# EIGHT_29.net
KiCad netlist of a schematic drawn in Altium Designer
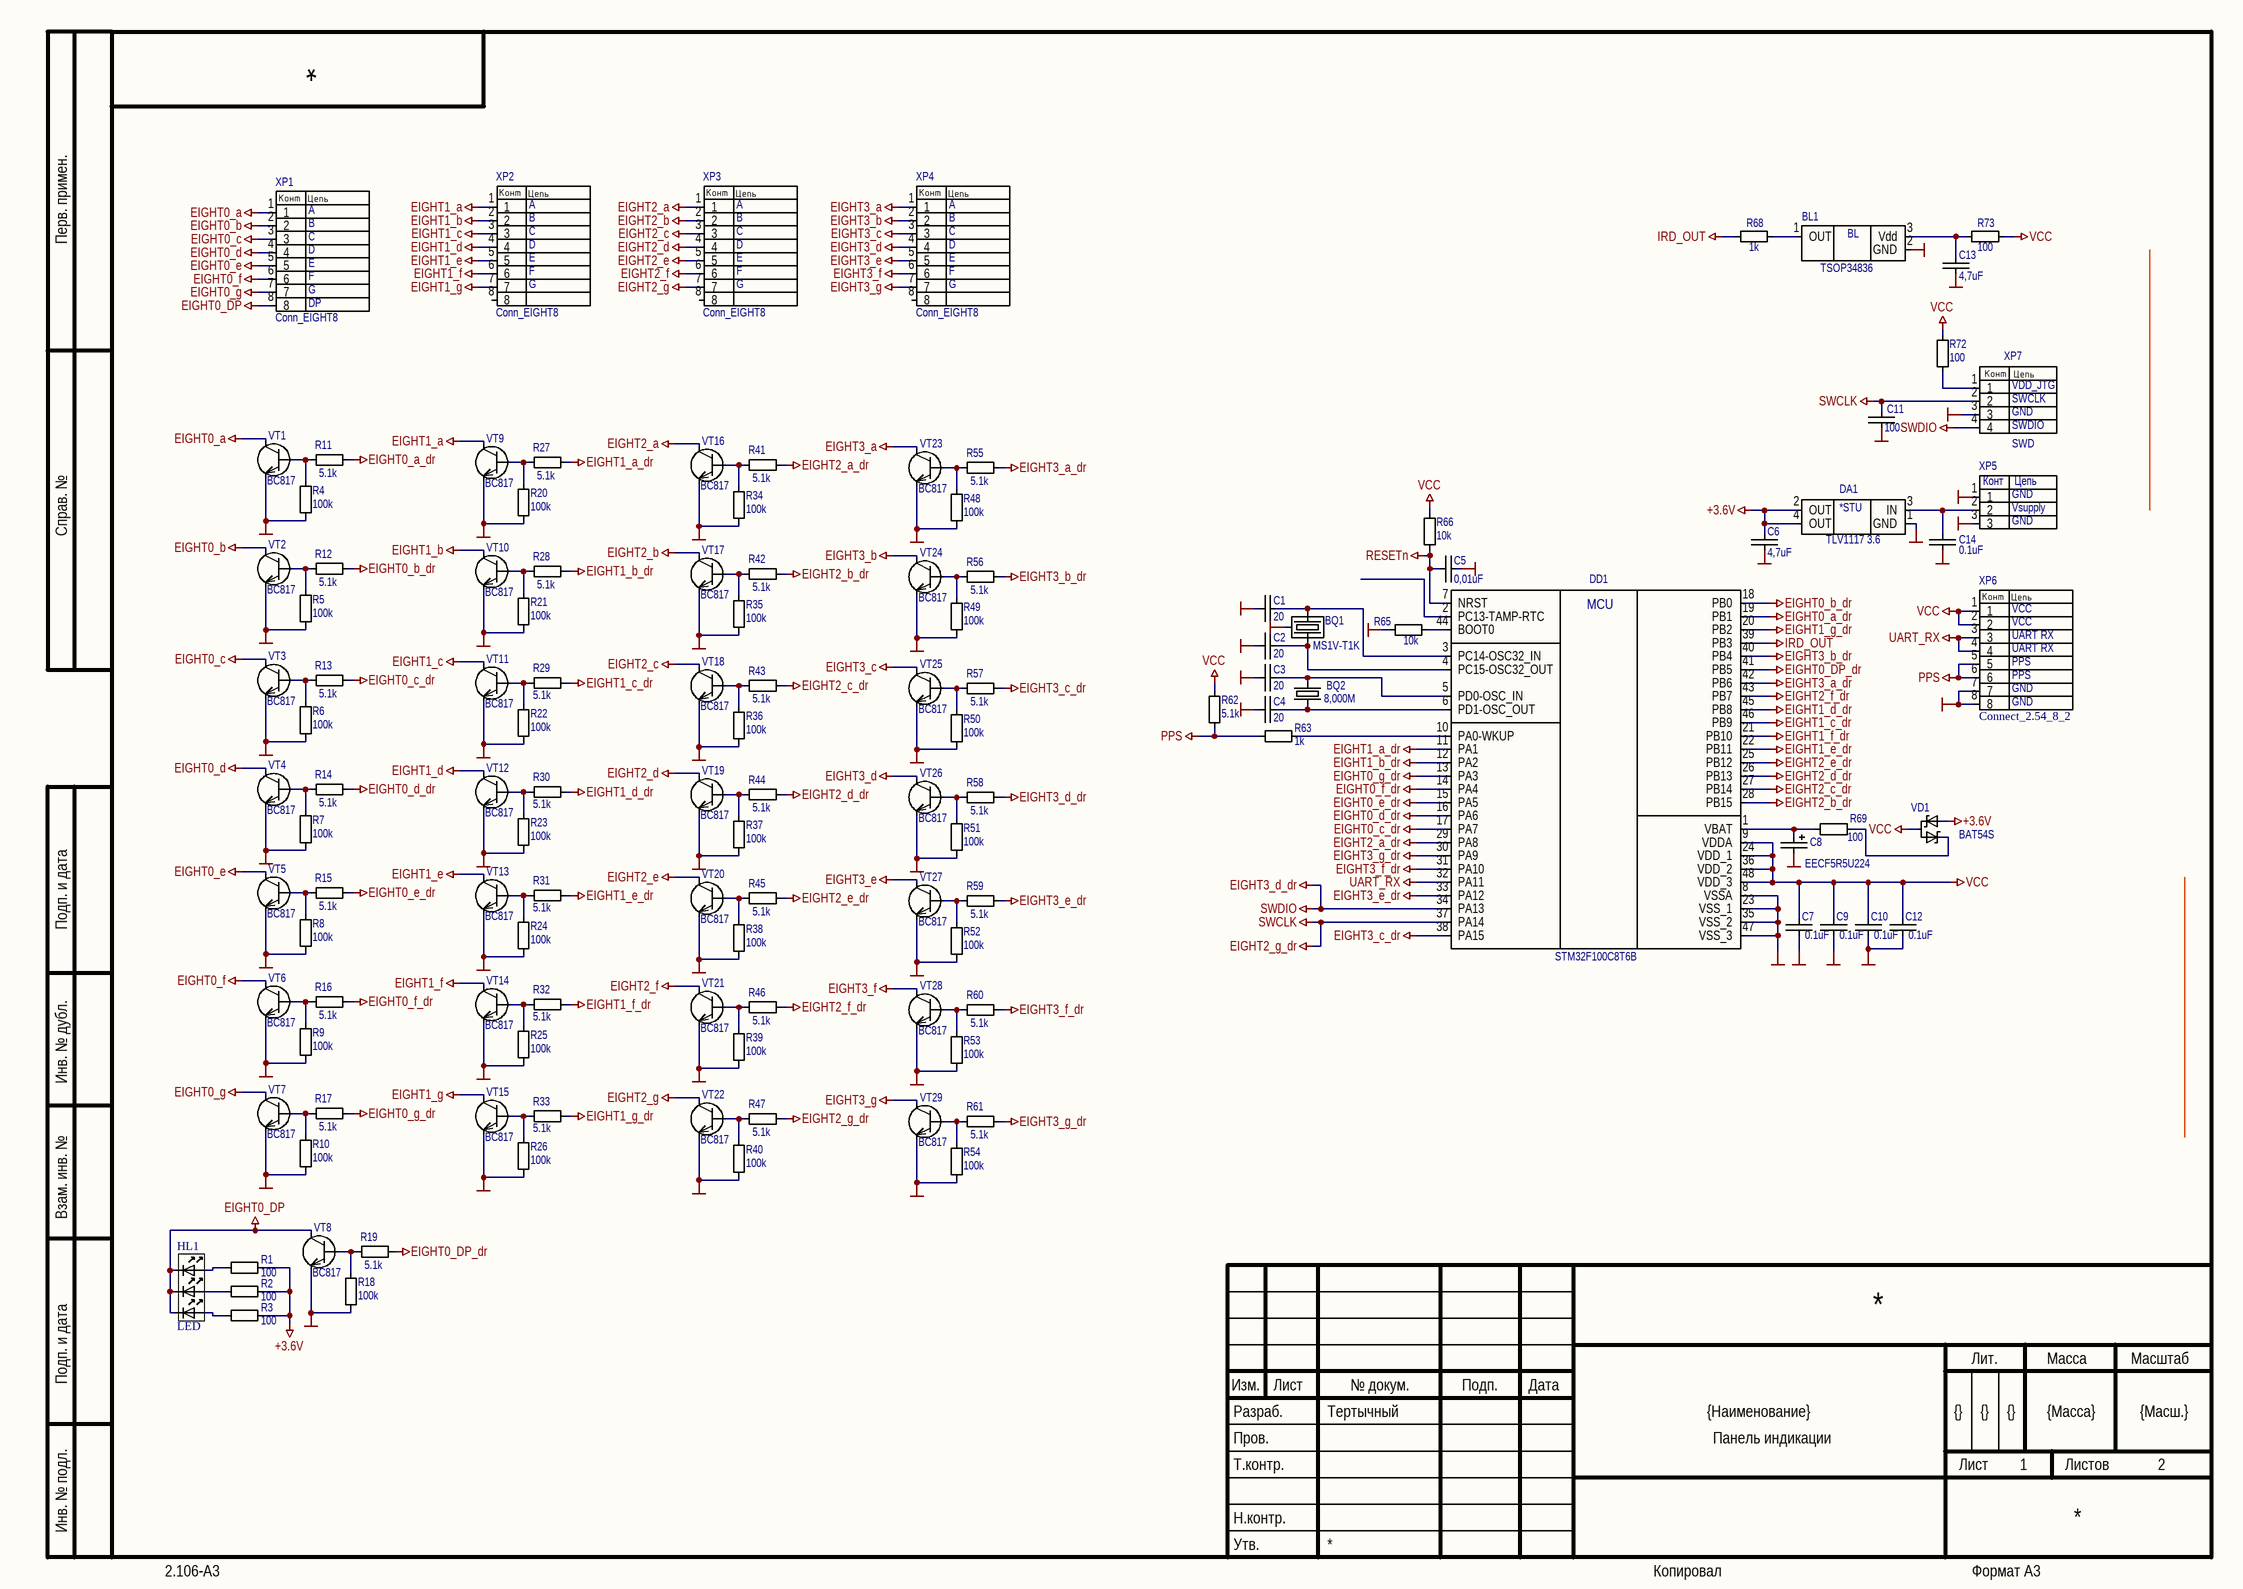
[diagram p0: EIGHT_29.SchDoc]

(export (version "E")
  (design (tool "Eeschema 10.0.6"))
  (components
    (comp (ref "BL1")
      (value "TSOP34836")
      (footprint "TSOP348xx -landed")
      (description "IR Receiver module")
      (fields (field (name "MANUFACTURER") "Vishay"))
      (libsource (lib "PANEL") (part "TSOP348xx_landed"))
    )
    (comp (ref "BQ1")
      (value "MS1V-T1K")
      (footprint "Quartz32k")
      (description "MS1V-T1K Quartz 32kHz 6pF")
      (fields (field (name "PART NUMBER") "MS1V-T1K 32.768kHZ 7pF"))
      (libsource (lib "PANEL") (part "MS1V-T1K"))
    )
    (comp (ref "BQ2")
      (value "8,000M")
      (footprint "HC 49SM")
      (description "Crystal oscillator")
      (fields (field (name "MANUFACTURER") "STRONG") (field (name "PART NUMBER") "HC49SM-8.000MHZ-20PF"))
      (libsource (lib "PANEL") (part "BQ_HC 49SM"))
    )
    (comp (ref "C1")
      (value "20")
      (footprint "Cap_0805")
      (description "20pF 100V 5% NPO")
      (fields (field (name "MANUFACTURER") "AVX") (field (name "PART NUMBER") "GRM2165C1H200J"))
      (libsource (lib "PANEL") (part "Cap_0805"))
    )
    (comp (ref "C2")
      (value "20")
      (footprint "Cap_0805")
      (description "20pF 100V 5% NPO")
      (fields (field (name "MANUFACTURER") "AVX") (field (name "PART NUMBER") "GRM2165C1H200J"))
      (libsource (lib "PANEL") (part "Cap_0805"))
    )
    (comp (ref "C3")
      (value "20")
      (footprint "Cap_0805")
      (description "20pF 100V 5% NPO")
      (fields (field (name "MANUFACTURER") "AVX") (field (name "PART NUMBER") "GRM2165C1H200J"))
      (libsource (lib "PANEL") (part "Cap_0805"))
    )
    (comp (ref "C4")
      (value "20")
      (footprint "Cap_0805")
      (description "20pF 100V 5% NPO")
      (fields (field (name "MANUFACTURER") "AVX") (field (name "PART NUMBER") "GRM2165C1H200J"))
      (libsource (lib "PANEL") (part "Cap_0805"))
    )
    (comp (ref "C5")
      (value "0,01uF")
      (footprint "Cap_0805")
      (description "0805 0.01uF 10V X7R 10%")
      (fields (field (name "MANUFACTURER") "AVX") (field (name "PART NUMBER") "08051C103KAT2A"))
      (libsource (lib "PANEL") (part "Cap_0805"))
    )
    (comp (ref "C6")
      (value "4,7uF")
      (footprint "Cap_0805")
      (description "4.7uF 16V X7R 10%")
      (fields (field (name "MANUFACTURER") "AVX") (field (name "PART NUMBER") "0805YC475KAT2A"))
      (libsource (lib "PANEL") (part "Cap_0805"))
    )
    (comp (ref "C7") (value "0.1uF") (footprint "CAP_0805") (libsource (lib "EIGHT_29") (part "Cap_0805")))
    (comp (ref "C8")
      (value "EECF5R5U224")
      (footprint "EECF5R5U224")
      (fields (field (name "MANUFACTURER") "PANASONIC"))
      (libsource (lib "EIGHT_29") (part "EECF5R5U224"))
    )
    (comp (ref "C9") (value "0.1uF") (footprint "CAP_0805") (libsource (lib "EIGHT_29") (part "Cap_0805")))
    (comp (ref "C10") (value "0.1uF") (footprint "CAP_0805") (libsource (lib "EIGHT_29") (part "Cap_0805")))
    (comp (ref "C11")
      (value "100")
      (footprint "Cap_0805")
      (description "0805 100pF 50V X7R 10%")
      (fields (field (name "MANUFACTURER") "AVX") (field (name "PART NUMBER") "08055C101KAT2A"))
      (libsource (lib "PANEL") (part "Cap_0805"))
    )
    (comp (ref "C12") (value "0.1uF") (footprint "CAP_0805") (libsource (lib "EIGHT_29") (part "Cap_0805")))
    (comp (ref "C13")
      (value "4,7uF")
      (footprint "Cap_0805")
      (description "4.7uF 16V X7R 10%")
      (fields (field (name "MANUFACTURER") "AVX") (field (name "PART NUMBER") "0805YC475KAT2A"))
      (libsource (lib "PANEL") (part "Cap_0805"))
    )
    (comp (ref "C14") (value "0.1uF") (footprint "CAP_0805") (libsource (lib "EIGHT_29") (part "Cap_0805")))
    (comp (ref "DA1")
      (value "TLV1117 3.6")
      (footprint "SOT223")
      (description "TLV1117-sot223")
      (fields (field (name "MANUFACTURER") "Microchip") (field (name "PART NUMBER") "TLV1117"))
      (libsource (lib "EIGHT_29") (part "TLV1117"))
    )
    (comp (ref "DD1")
      (value "STM32F100C8T6B")
      (footprint "LQFP48")
      (description "ARM Cortex-M3 MCU")
      (fields (field (name "MANUFACTURER") "ST"))
      (libsource (lib "PANEL") (part "STM32F100C8T6B"))
    )
    (comp (ref "HL1")
      (value "LED")
      (footprint "LED5050")
      (description "SMD5050")
      (fields (field (name "MANUFACTURER") "DIODES"))
      (libsource (lib "EIGHT_29") (part "LED SMD5050"))
    )
    (comp (ref "R1")
      (value "100")
      (footprint "Res_0603")
      (description "0805 0.125W 100 Ohms 5%")
      (fields (field (name "MANUFACTURER") "Vishay") (field (name "PART NUMBER") "CRCW0805100RJNEA"))
      (libsource (lib "PANEL") (part "Res_0805"))
    )
    (comp (ref "R2")
      (value "100")
      (footprint "Res_0603")
      (description "0805 0.125W 100 Ohms 5%")
      (fields (field (name "MANUFACTURER") "Vishay") (field (name "PART NUMBER") "CRCW0805100RJNEA"))
      (libsource (lib "PANEL") (part "Res_0805"))
    )
    (comp (ref "R3")
      (value "100")
      (footprint "Res_0603")
      (description "0805 0.125W 100 Ohms 5%")
      (fields (field (name "MANUFACTURER") "Vishay") (field (name "PART NUMBER") "CRCW0805100RJNEA"))
      (libsource (lib "PANEL") (part "Res_0805"))
    )
    (comp (ref "R4")
      (value "100k")
      (footprint "Res_0603")
      (description "0805, 0.125W, 100 kOhm, 5 %")
      (fields (field (name "MANUFACTURER") "Bourns") (field (name "PART NUMBER") "CR0805-JW-104ELF"))
      (libsource (lib "PANEL") (part "Res_0805"))
    )
    (comp (ref "R5")
      (value "100k")
      (footprint "Res_0603")
      (description "0805, 0.125W, 100 kOhm, 5 %")
      (fields (field (name "MANUFACTURER") "Bourns") (field (name "PART NUMBER") "CR0805-JW-104ELF"))
      (libsource (lib "PANEL") (part "Res_0805"))
    )
    (comp (ref "R6")
      (value "100k")
      (footprint "Res_0603")
      (description "0805, 0.125W, 100 kOhm, 5 %")
      (fields (field (name "MANUFACTURER") "Bourns") (field (name "PART NUMBER") "CR0805-JW-104ELF"))
      (libsource (lib "PANEL") (part "Res_0805"))
    )
    (comp (ref "R7")
      (value "100k")
      (footprint "Res_0603")
      (description "0805, 0.125W, 100 kOhm, 5 %")
      (fields (field (name "MANUFACTURER") "Bourns") (field (name "PART NUMBER") "CR0805-JW-104ELF"))
      (libsource (lib "PANEL") (part "Res_0805"))
    )
    (comp (ref "R8")
      (value "100k")
      (footprint "Res_0603")
      (description "0805, 0.125W, 100 kOhm, 5 %")
      (fields (field (name "MANUFACTURER") "Bourns") (field (name "PART NUMBER") "CR0805-JW-104ELF"))
      (libsource (lib "PANEL") (part "Res_0805"))
    )
    (comp (ref "R9")
      (value "100k")
      (footprint "Res_0603")
      (description "0805, 0.125W, 100 kOhm, 5 %")
      (fields (field (name "MANUFACTURER") "Bourns") (field (name "PART NUMBER") "CR0805-JW-104ELF"))
      (libsource (lib "PANEL") (part "Res_0805"))
    )
    (comp (ref "R10")
      (value "100k")
      (footprint "Res_0603")
      (description "0805, 0.125W, 100 kOhm, 5 %")
      (fields (field (name "MANUFACTURER") "Bourns") (field (name "PART NUMBER") "CR0805-JW-104ELF"))
      (libsource (lib "PANEL") (part "Res_0805"))
    )
    (comp (ref "R11")
      (value "5.1k")
      (footprint "Res_0603")
      (description "0805, 0.125W, 5.1 kOhm, 5 %")
      (fields (field (name "MANUFACTURER") "Vishay") (field (name "PART NUMBER") "CRCW0805K10JNTA"))
      (libsource (lib "PANEL") (part "Res_0805"))
    )
    (comp (ref "R12")
      (value "5.1k")
      (footprint "Res_0603")
      (description "0805, 0.125W, 5.1 kOhm, 5 %")
      (fields (field (name "MANUFACTURER") "Vishay") (field (name "PART NUMBER") "CRCW0805K10JNTA"))
      (libsource (lib "PANEL") (part "Res_0805"))
    )
    (comp (ref "R13")
      (value "5.1k")
      (footprint "Res_0603")
      (description "0805, 0.125W, 5.1 kOhm, 5 %")
      (fields (field (name "MANUFACTURER") "Vishay") (field (name "PART NUMBER") "CRCW0805K10JNTA"))
      (libsource (lib "PANEL") (part "Res_0805"))
    )
    (comp (ref "R14")
      (value "5.1k")
      (footprint "Res_0603")
      (description "0805, 0.125W, 5.1 kOhm, 5 %")
      (fields (field (name "MANUFACTURER") "Vishay") (field (name "PART NUMBER") "CRCW0805K10JNTA"))
      (libsource (lib "PANEL") (part "Res_0805"))
    )
    (comp (ref "R15")
      (value "5.1k")
      (footprint "Res_0603")
      (description "0805, 0.125W, 5.1 kOhm, 5 %")
      (fields (field (name "MANUFACTURER") "Vishay") (field (name "PART NUMBER") "CRCW0805K10JNTA"))
      (libsource (lib "PANEL") (part "Res_0805"))
    )
    (comp (ref "R16")
      (value "5.1k")
      (footprint "Res_0603")
      (description "0805, 0.125W, 5.1 kOhm, 5 %")
      (fields (field (name "MANUFACTURER") "Vishay") (field (name "PART NUMBER") "CRCW0805K10JNTA"))
      (libsource (lib "PANEL") (part "Res_0805"))
    )
    (comp (ref "R17")
      (value "5.1k")
      (footprint "Res_0603")
      (description "0805, 0.125W, 5.1 kOhm, 5 %")
      (fields (field (name "MANUFACTURER") "Vishay") (field (name "PART NUMBER") "CRCW0805K10JNTA"))
      (libsource (lib "PANEL") (part "Res_0805"))
    )
    (comp (ref "R18")
      (value "100k")
      (footprint "Res_0603")
      (description "0805, 0.125W, 100 kOhm, 5 %")
      (fields (field (name "MANUFACTURER") "Bourns") (field (name "PART NUMBER") "CR0805-JW-104ELF"))
      (libsource (lib "PANEL") (part "Res_0805"))
    )
    (comp (ref "R19")
      (value "5.1k")
      (footprint "Res_0603")
      (description "0805, 0.125W, 5.1 kOhm, 5 %")
      (fields (field (name "MANUFACTURER") "Vishay") (field (name "PART NUMBER") "CRCW0805K10JNTA"))
      (libsource (lib "PANEL") (part "Res_0805"))
    )
    (comp (ref "R20")
      (value "100k")
      (footprint "Res_0603")
      (description "0805, 0.125W, 100 kOhm, 5 %")
      (fields (field (name "MANUFACTURER") "Bourns") (field (name "PART NUMBER") "CR0805-JW-104ELF"))
      (libsource (lib "PANEL") (part "Res_0805"))
    )
    (comp (ref "R21")
      (value "100k")
      (footprint "Res_0603")
      (description "0805, 0.125W, 100 kOhm, 5 %")
      (fields (field (name "MANUFACTURER") "Bourns") (field (name "PART NUMBER") "CR0805-JW-104ELF"))
      (libsource (lib "PANEL") (part "Res_0805"))
    )
    (comp (ref "R22")
      (value "100k")
      (footprint "Res_0603")
      (description "0805, 0.125W, 100 kOhm, 5 %")
      (fields (field (name "MANUFACTURER") "Bourns") (field (name "PART NUMBER") "CR0805-JW-104ELF"))
      (libsource (lib "PANEL") (part "Res_0805"))
    )
    (comp (ref "R23")
      (value "100k")
      (footprint "Res_0603")
      (description "0805, 0.125W, 100 kOhm, 5 %")
      (fields (field (name "MANUFACTURER") "Bourns") (field (name "PART NUMBER") "CR0805-JW-104ELF"))
      (libsource (lib "PANEL") (part "Res_0805"))
    )
    (comp (ref "R24")
      (value "100k")
      (footprint "Res_0603")
      (description "0805, 0.125W, 100 kOhm, 5 %")
      (fields (field (name "MANUFACTURER") "Bourns") (field (name "PART NUMBER") "CR0805-JW-104ELF"))
      (libsource (lib "PANEL") (part "Res_0805"))
    )
    (comp (ref "R25")
      (value "100k")
      (footprint "Res_0603")
      (description "0805, 0.125W, 100 kOhm, 5 %")
      (fields (field (name "MANUFACTURER") "Bourns") (field (name "PART NUMBER") "CR0805-JW-104ELF"))
      (libsource (lib "PANEL") (part "Res_0805"))
    )
    (comp (ref "R26")
      (value "100k")
      (footprint "Res_0603")
      (description "0805, 0.125W, 100 kOhm, 5 %")
      (fields (field (name "MANUFACTURER") "Bourns") (field (name "PART NUMBER") "CR0805-JW-104ELF"))
      (libsource (lib "PANEL") (part "Res_0805"))
    )
    (comp (ref "R27")
      (value "5.1k")
      (footprint "Res_0603")
      (description "0805, 0.125W, 5.1 kOhm, 5 %")
      (fields (field (name "MANUFACTURER") "Vishay") (field (name "PART NUMBER") "CRCW0805K10JNTA"))
      (libsource (lib "PANEL") (part "Res_0805"))
    )
    (comp (ref "R28")
      (value "5.1k")
      (footprint "Res_0603")
      (description "0805, 0.125W, 5.1 kOhm, 5 %")
      (fields (field (name "MANUFACTURER") "Vishay") (field (name "PART NUMBER") "CRCW0805K10JNTA"))
      (libsource (lib "PANEL") (part "Res_0805"))
    )
    (comp (ref "R29")
      (value "5.1k")
      (footprint "Res_0603")
      (description "0805, 0.125W, 5.1 kOhm, 5 %")
      (fields (field (name "MANUFACTURER") "Vishay") (field (name "PART NUMBER") "CRCW0805K10JNTA"))
      (libsource (lib "PANEL") (part "Res_0805"))
    )
    (comp (ref "R30")
      (value "5.1k")
      (footprint "Res_0603")
      (description "0805, 0.125W, 5.1 kOhm, 5 %")
      (fields (field (name "MANUFACTURER") "Vishay") (field (name "PART NUMBER") "CRCW0805K10JNTA"))
      (libsource (lib "PANEL") (part "Res_0805"))
    )
    (comp (ref "R31")
      (value "5.1k")
      (footprint "Res_0603")
      (description "0805, 0.125W, 5.1 kOhm, 5 %")
      (fields (field (name "MANUFACTURER") "Vishay") (field (name "PART NUMBER") "CRCW0805K10JNTA"))
      (libsource (lib "PANEL") (part "Res_0805"))
    )
    (comp (ref "R32")
      (value "5.1k")
      (footprint "Res_0603")
      (description "0805, 0.125W, 5.1 kOhm, 5 %")
      (fields (field (name "MANUFACTURER") "Vishay") (field (name "PART NUMBER") "CRCW0805K10JNTA"))
      (libsource (lib "PANEL") (part "Res_0805"))
    )
    (comp (ref "R33")
      (value "5.1k")
      (footprint "Res_0603")
      (description "0805, 0.125W, 5.1 kOhm, 5 %")
      (fields (field (name "MANUFACTURER") "Vishay") (field (name "PART NUMBER") "CRCW0805K10JNTA"))
      (libsource (lib "PANEL") (part "Res_0805"))
    )
    (comp (ref "R34")
      (value "100k")
      (footprint "Res_0603")
      (description "0805, 0.125W, 100 kOhm, 5 %")
      (fields (field (name "MANUFACTURER") "Bourns") (field (name "PART NUMBER") "CR0805-JW-104ELF"))
      (libsource (lib "PANEL") (part "Res_0805"))
    )
    (comp (ref "R35")
      (value "100k")
      (footprint "Res_0603")
      (description "0805, 0.125W, 100 kOhm, 5 %")
      (fields (field (name "MANUFACTURER") "Bourns") (field (name "PART NUMBER") "CR0805-JW-104ELF"))
      (libsource (lib "PANEL") (part "Res_0805"))
    )
    (comp (ref "R36")
      (value "100k")
      (footprint "Res_0603")
      (description "0805, 0.125W, 100 kOhm, 5 %")
      (fields (field (name "MANUFACTURER") "Bourns") (field (name "PART NUMBER") "CR0805-JW-104ELF"))
      (libsource (lib "PANEL") (part "Res_0805"))
    )
    (comp (ref "R37")
      (value "100k")
      (footprint "Res_0603")
      (description "0805, 0.125W, 100 kOhm, 5 %")
      (fields (field (name "MANUFACTURER") "Bourns") (field (name "PART NUMBER") "CR0805-JW-104ELF"))
      (libsource (lib "PANEL") (part "Res_0805"))
    )
    (comp (ref "R38")
      (value "100k")
      (footprint "Res_0603")
      (description "0805, 0.125W, 100 kOhm, 5 %")
      (fields (field (name "MANUFACTURER") "Bourns") (field (name "PART NUMBER") "CR0805-JW-104ELF"))
      (libsource (lib "PANEL") (part "Res_0805"))
    )
    (comp (ref "R39")
      (value "100k")
      (footprint "Res_0603")
      (description "0805, 0.125W, 100 kOhm, 5 %")
      (fields (field (name "MANUFACTURER") "Bourns") (field (name "PART NUMBER") "CR0805-JW-104ELF"))
      (libsource (lib "PANEL") (part "Res_0805"))
    )
    (comp (ref "R40")
      (value "100k")
      (footprint "Res_0603")
      (description "0805, 0.125W, 100 kOhm, 5 %")
      (fields (field (name "MANUFACTURER") "Bourns") (field (name "PART NUMBER") "CR0805-JW-104ELF"))
      (libsource (lib "PANEL") (part "Res_0805"))
    )
    (comp (ref "R41")
      (value "5.1k")
      (footprint "Res_0603")
      (description "0805, 0.125W, 5.1 kOhm, 5 %")
      (fields (field (name "MANUFACTURER") "Vishay") (field (name "PART NUMBER") "CRCW0805K10JNTA"))
      (libsource (lib "PANEL") (part "Res_0805"))
    )
    (comp (ref "R42")
      (value "5.1k")
      (footprint "Res_0603")
      (description "0805, 0.125W, 5.1 kOhm, 5 %")
      (fields (field (name "MANUFACTURER") "Vishay") (field (name "PART NUMBER") "CRCW0805K10JNTA"))
      (libsource (lib "PANEL") (part "Res_0805"))
    )
    (comp (ref "R43")
      (value "5.1k")
      (footprint "Res_0603")
      (description "0805, 0.125W, 5.1 kOhm, 5 %")
      (fields (field (name "MANUFACTURER") "Vishay") (field (name "PART NUMBER") "CRCW0805K10JNTA"))
      (libsource (lib "PANEL") (part "Res_0805"))
    )
    (comp (ref "R44")
      (value "5.1k")
      (footprint "Res_0603")
      (description "0805, 0.125W, 5.1 kOhm, 5 %")
      (fields (field (name "MANUFACTURER") "Vishay") (field (name "PART NUMBER") "CRCW0805K10JNTA"))
      (libsource (lib "PANEL") (part "Res_0805"))
    )
    (comp (ref "R45")
      (value "5.1k")
      (footprint "Res_0603")
      (description "0805, 0.125W, 5.1 kOhm, 5 %")
      (fields (field (name "MANUFACTURER") "Vishay") (field (name "PART NUMBER") "CRCW0805K10JNTA"))
      (libsource (lib "PANEL") (part "Res_0805"))
    )
    (comp (ref "R46")
      (value "5.1k")
      (footprint "Res_0603")
      (description "0805, 0.125W, 5.1 kOhm, 5 %")
      (fields (field (name "MANUFACTURER") "Vishay") (field (name "PART NUMBER") "CRCW0805K10JNTA"))
      (libsource (lib "PANEL") (part "Res_0805"))
    )
    (comp (ref "R47")
      (value "5.1k")
      (footprint "Res_0603")
      (description "0805, 0.125W, 5.1 kOhm, 5 %")
      (fields (field (name "MANUFACTURER") "Vishay") (field (name "PART NUMBER") "CRCW0805K10JNTA"))
      (libsource (lib "PANEL") (part "Res_0805"))
    )
    (comp (ref "R48")
      (value "100k")
      (footprint "Res_0603")
      (description "0805, 0.125W, 100 kOhm, 5 %")
      (fields (field (name "MANUFACTURER") "Bourns") (field (name "PART NUMBER") "CR0805-JW-104ELF"))
      (libsource (lib "PANEL") (part "Res_0805"))
    )
    (comp (ref "R49")
      (value "100k")
      (footprint "Res_0603")
      (description "0805, 0.125W, 100 kOhm, 5 %")
      (fields (field (name "MANUFACTURER") "Bourns") (field (name "PART NUMBER") "CR0805-JW-104ELF"))
      (libsource (lib "PANEL") (part "Res_0805"))
    )
    (comp (ref "R50")
      (value "100k")
      (footprint "Res_0603")
      (description "0805, 0.125W, 100 kOhm, 5 %")
      (fields (field (name "MANUFACTURER") "Bourns") (field (name "PART NUMBER") "CR0805-JW-104ELF"))
      (libsource (lib "PANEL") (part "Res_0805"))
    )
    (comp (ref "R51")
      (value "100k")
      (footprint "Res_0603")
      (description "0805, 0.125W, 100 kOhm, 5 %")
      (fields (field (name "MANUFACTURER") "Bourns") (field (name "PART NUMBER") "CR0805-JW-104ELF"))
      (libsource (lib "PANEL") (part "Res_0805"))
    )
    (comp (ref "R52")
      (value "100k")
      (footprint "Res_0603")
      (description "0805, 0.125W, 100 kOhm, 5 %")
      (fields (field (name "MANUFACTURER") "Bourns") (field (name "PART NUMBER") "CR0805-JW-104ELF"))
      (libsource (lib "PANEL") (part "Res_0805"))
    )
    (comp (ref "R53")
      (value "100k")
      (footprint "Res_0603")
      (description "0805, 0.125W, 100 kOhm, 5 %")
      (fields (field (name "MANUFACTURER") "Bourns") (field (name "PART NUMBER") "CR0805-JW-104ELF"))
      (libsource (lib "PANEL") (part "Res_0805"))
    )
    (comp (ref "R54")
      (value "100k")
      (footprint "Res_0603")
      (description "0805, 0.125W, 100 kOhm, 5 %")
      (fields (field (name "MANUFACTURER") "Bourns") (field (name "PART NUMBER") "CR0805-JW-104ELF"))
      (libsource (lib "PANEL") (part "Res_0805"))
    )
    (comp (ref "R55")
      (value "5.1k")
      (footprint "Res_0603")
      (description "0805, 0.125W, 5.1 kOhm, 5 %")
      (fields (field (name "MANUFACTURER") "Vishay") (field (name "PART NUMBER") "CRCW0805K10JNTA"))
      (libsource (lib "PANEL") (part "Res_0805"))
    )
    (comp (ref "R56")
      (value "5.1k")
      (footprint "Res_0603")
      (description "0805, 0.125W, 5.1 kOhm, 5 %")
      (fields (field (name "MANUFACTURER") "Vishay") (field (name "PART NUMBER") "CRCW0805K10JNTA"))
      (libsource (lib "PANEL") (part "Res_0805"))
    )
    (comp (ref "R57")
      (value "5.1k")
      (footprint "Res_0603")
      (description "0805, 0.125W, 5.1 kOhm, 5 %")
      (fields (field (name "MANUFACTURER") "Vishay") (field (name "PART NUMBER") "CRCW0805K10JNTA"))
      (libsource (lib "PANEL") (part "Res_0805"))
    )
    (comp (ref "R58")
      (value "5.1k")
      (footprint "Res_0603")
      (description "0805, 0.125W, 5.1 kOhm, 5 %")
      (fields (field (name "MANUFACTURER") "Vishay") (field (name "PART NUMBER") "CRCW0805K10JNTA"))
      (libsource (lib "PANEL") (part "Res_0805"))
    )
    (comp (ref "R59")
      (value "5.1k")
      (footprint "Res_0603")
      (description "0805, 0.125W, 5.1 kOhm, 5 %")
      (fields (field (name "MANUFACTURER") "Vishay") (field (name "PART NUMBER") "CRCW0805K10JNTA"))
      (libsource (lib "PANEL") (part "Res_0805"))
    )
    (comp (ref "R60")
      (value "5.1k")
      (footprint "Res_0603")
      (description "0805, 0.125W, 5.1 kOhm, 5 %")
      (fields (field (name "MANUFACTURER") "Vishay") (field (name "PART NUMBER") "CRCW0805K10JNTA"))
      (libsource (lib "PANEL") (part "Res_0805"))
    )
    (comp (ref "R61")
      (value "5.1k")
      (footprint "Res_0603")
      (description "0805, 0.125W, 5.1 kOhm, 5 %")
      (fields (field (name "MANUFACTURER") "Vishay") (field (name "PART NUMBER") "CRCW0805K10JNTA"))
      (libsource (lib "PANEL") (part "Res_0805"))
    )
    (comp (ref "R62")
      (value "5.1k")
      (footprint "Res_0603")
      (description "0805, 0.125W, 5.1 kOhm, 5 %")
      (fields (field (name "MANUFACTURER") "Vishay") (field (name "PART NUMBER") "CRCW0805K10JNTA"))
      (libsource (lib "PANEL") (part "Res_0805"))
    )
    (comp (ref "R63")
      (value "1k")
      (footprint "Res_0603")
      (description "0805, 0.125W, 1 kOhm, 5 %")
      (fields (field (name "MANUFACTURER") "Bourns") (field (name "PART NUMBER") "CR0805-JW-102ELF"))
      (libsource (lib "PANEL") (part "Res_0805"))
    )
    (comp (ref "R65")
      (value "10k")
      (footprint "Res_0603")
      (description "0805, 0.125W, 10 kOhm, 5 %")
      (fields (field (name "MANUFACTURER") "Vishay") (field (name "PART NUMBER") "CRCW080510K0JNTA"))
      (libsource (lib "PANEL") (part "Res_0805"))
    )
    (comp (ref "R66")
      (value "10k")
      (footprint "Res_0603")
      (description "0805, 0.125W, 10 kOhm, 5 %")
      (fields (field (name "MANUFACTURER") "Vishay") (field (name "PART NUMBER") "CRCW080510K0JNTA"))
      (libsource (lib "PANEL") (part "Res_0805"))
    )
    (comp (ref "R68")
      (value "1k")
      (footprint "Res_0603")
      (description "0805 1k Ohm 5% 0.125W")
      (fields (field (name "MANUFACTURER") "Vishay") (field (name "PART NUMBER") "CRCW08051K00JNTA"))
      (libsource (lib "PANEL") (part "Res_0805"))
    )
    (comp (ref "R69")
      (value "100")
      (footprint "Res_0603")
      (description "0805 0.125W 100 Ohms 5%")
      (fields (field (name "MANUFACTURER") "Vishay") (field (name "PART NUMBER") "CRCW0805100RJNEA"))
      (libsource (lib "PANEL") (part "Res_0805"))
    )
    (comp (ref "R72")
      (value "100")
      (footprint "Res_0603")
      (description "0805 0.125W 100 Ohms 5%")
      (fields (field (name "MANUFACTURER") "Vishay") (field (name "PART NUMBER") "CRCW0805100RJNEA"))
      (libsource (lib "PANEL") (part "Res_0805"))
    )
    (comp (ref "R73")
      (value "100")
      (footprint "Res_0603")
      (description "0805 0.125W 100 Ohms 5%")
      (fields (field (name "MANUFACTURER") "Vishay") (field (name "PART NUMBER") "CRCW0805100RJNEA"))
      (libsource (lib "PANEL") (part "Res_0805"))
    )
    (comp (ref "VD1") (value "BAT54S") (footprint "SOT-23") (libsource (lib "PANEL") (part "BAT54S")))
    (comp (ref "VT1")
      (value "BC817")
      (footprint "SOT-23")
      (description "BC817 NPN")
      (fields (field (name "MANUFACTURER") "Discrete Semiconductors"))
      (libsource (lib "PANEL") (part "NPN_SOT23_DIG_1"))
    )
    (comp (ref "VT2")
      (value "BC817")
      (footprint "SOT-23")
      (description "BC817 NPN")
      (fields (field (name "MANUFACTURER") "Discrete Semiconductors"))
      (libsource (lib "PANEL") (part "NPN_SOT23_DIG_1"))
    )
    (comp (ref "VT3")
      (value "BC817")
      (footprint "SOT-23")
      (description "BC817 NPN")
      (fields (field (name "MANUFACTURER") "Discrete Semiconductors"))
      (libsource (lib "PANEL") (part "NPN_SOT23_DIG_1"))
    )
    (comp (ref "VT4")
      (value "BC817")
      (footprint "SOT-23")
      (description "BC817 NPN")
      (fields (field (name "MANUFACTURER") "Discrete Semiconductors"))
      (libsource (lib "PANEL") (part "NPN_SOT23_DIG_1"))
    )
    (comp (ref "VT5")
      (value "BC817")
      (footprint "SOT-23")
      (description "BC817 NPN")
      (fields (field (name "MANUFACTURER") "Discrete Semiconductors"))
      (libsource (lib "PANEL") (part "NPN_SOT23_DIG_1"))
    )
    (comp (ref "VT6")
      (value "BC817")
      (footprint "SOT-23")
      (description "BC817 NPN")
      (fields (field (name "MANUFACTURER") "Discrete Semiconductors"))
      (libsource (lib "PANEL") (part "NPN_SOT23_DIG_1"))
    )
    (comp (ref "VT7")
      (value "BC817")
      (footprint "SOT-23")
      (description "BC817 NPN")
      (fields (field (name "MANUFACTURER") "Discrete Semiconductors"))
      (libsource (lib "PANEL") (part "NPN_SOT23_DIG_1"))
    )
    (comp (ref "VT8")
      (value "BC817")
      (footprint "SOT-23")
      (description "BC817 NPN")
      (fields (field (name "MANUFACTURER") "Discrete Semiconductors"))
      (libsource (lib "PANEL") (part "NPN_SOT23_DIG_1"))
    )
    (comp (ref "VT9")
      (value "BC817")
      (footprint "SOT-23")
      (description "BC817 NPN")
      (fields (field (name "MANUFACTURER") "Discrete Semiconductors"))
      (libsource (lib "PANEL") (part "NPN_SOT23_DIG_1"))
    )
    (comp (ref "VT10")
      (value "BC817")
      (footprint "SOT-23")
      (description "BC817 NPN")
      (fields (field (name "MANUFACTURER") "Discrete Semiconductors"))
      (libsource (lib "PANEL") (part "NPN_SOT23_DIG_1"))
    )
    (comp (ref "VT11")
      (value "BC817")
      (footprint "SOT-23")
      (description "BC817 NPN")
      (fields (field (name "MANUFACTURER") "Discrete Semiconductors"))
      (libsource (lib "PANEL") (part "NPN_SOT23_DIG_1"))
    )
    (comp (ref "VT12")
      (value "BC817")
      (footprint "SOT-23")
      (description "BC817 NPN")
      (fields (field (name "MANUFACTURER") "Discrete Semiconductors"))
      (libsource (lib "PANEL") (part "NPN_SOT23_DIG_1"))
    )
    (comp (ref "VT13")
      (value "BC817")
      (footprint "SOT-23")
      (description "BC817 NPN")
      (fields (field (name "MANUFACTURER") "Discrete Semiconductors"))
      (libsource (lib "PANEL") (part "NPN_SOT23_DIG_1"))
    )
    (comp (ref "VT14")
      (value "BC817")
      (footprint "SOT-23")
      (description "BC817 NPN")
      (fields (field (name "MANUFACTURER") "Discrete Semiconductors"))
      (libsource (lib "PANEL") (part "NPN_SOT23_DIG_1"))
    )
    (comp (ref "VT15")
      (value "BC817")
      (footprint "SOT-23")
      (description "BC817 NPN")
      (fields (field (name "MANUFACTURER") "Discrete Semiconductors"))
      (libsource (lib "PANEL") (part "NPN_SOT23_DIG_1"))
    )
    (comp (ref "VT16")
      (value "BC817")
      (footprint "SOT-23")
      (description "BC817 NPN")
      (fields (field (name "MANUFACTURER") "Discrete Semiconductors"))
      (libsource (lib "PANEL") (part "NPN_SOT23_DIG_1"))
    )
    (comp (ref "VT17")
      (value "BC817")
      (footprint "SOT-23")
      (description "BC817 NPN")
      (fields (field (name "MANUFACTURER") "Discrete Semiconductors"))
      (libsource (lib "PANEL") (part "NPN_SOT23_DIG_1"))
    )
    (comp (ref "VT18")
      (value "BC817")
      (footprint "SOT-23")
      (description "BC817 NPN")
      (fields (field (name "MANUFACTURER") "Discrete Semiconductors"))
      (libsource (lib "PANEL") (part "NPN_SOT23_DIG_1"))
    )
    (comp (ref "VT19")
      (value "BC817")
      (footprint "SOT-23")
      (description "BC817 NPN")
      (fields (field (name "MANUFACTURER") "Discrete Semiconductors"))
      (libsource (lib "PANEL") (part "NPN_SOT23_DIG_1"))
    )
    (comp (ref "VT20")
      (value "BC817")
      (footprint "SOT-23")
      (description "BC817 NPN")
      (fields (field (name "MANUFACTURER") "Discrete Semiconductors"))
      (libsource (lib "PANEL") (part "NPN_SOT23_DIG_1"))
    )
    (comp (ref "VT21")
      (value "BC817")
      (footprint "SOT-23")
      (description "BC817 NPN")
      (fields (field (name "MANUFACTURER") "Discrete Semiconductors"))
      (libsource (lib "PANEL") (part "NPN_SOT23_DIG_1"))
    )
    (comp (ref "VT22")
      (value "BC817")
      (footprint "SOT-23")
      (description "BC817 NPN")
      (fields (field (name "MANUFACTURER") "Discrete Semiconductors"))
      (libsource (lib "PANEL") (part "NPN_SOT23_DIG_1"))
    )
    (comp (ref "VT23")
      (value "BC817")
      (footprint "SOT-23")
      (description "BC817 NPN")
      (fields (field (name "MANUFACTURER") "Discrete Semiconductors"))
      (libsource (lib "PANEL") (part "NPN_SOT23_DIG_1"))
    )
    (comp (ref "VT24")
      (value "BC817")
      (footprint "SOT-23")
      (description "BC817 NPN")
      (fields (field (name "MANUFACTURER") "Discrete Semiconductors"))
      (libsource (lib "PANEL") (part "NPN_SOT23_DIG_1"))
    )
    (comp (ref "VT25")
      (value "BC817")
      (footprint "SOT-23")
      (description "BC817 NPN")
      (fields (field (name "MANUFACTURER") "Discrete Semiconductors"))
      (libsource (lib "PANEL") (part "NPN_SOT23_DIG_1"))
    )
    (comp (ref "VT26")
      (value "BC817")
      (footprint "SOT-23")
      (description "BC817 NPN")
      (fields (field (name "MANUFACTURER") "Discrete Semiconductors"))
      (libsource (lib "PANEL") (part "NPN_SOT23_DIG_1"))
    )
    (comp (ref "VT27")
      (value "BC817")
      (footprint "SOT-23")
      (description "BC817 NPN")
      (fields (field (name "MANUFACTURER") "Discrete Semiconductors"))
      (libsource (lib "PANEL") (part "NPN_SOT23_DIG_1"))
    )
    (comp (ref "VT28")
      (value "BC817")
      (footprint "SOT-23")
      (description "BC817 NPN")
      (fields (field (name "MANUFACTURER") "Discrete Semiconductors"))
      (libsource (lib "PANEL") (part "NPN_SOT23_DIG_1"))
    )
    (comp (ref "VT29")
      (value "BC817")
      (footprint "SOT-23")
      (description "BC817 NPN")
      (fields (field (name "MANUFACTURER") "Discrete Semiconductors"))
      (libsource (lib "PANEL") (part "NPN_SOT23_DIG_1"))
    )
    (comp (ref "XP1") (value "Conn_EIGHT8") (footprint "CONN2-8") (libsource (lib "") (part "Conn_EIGHT8_1")))
    (comp (ref "XP2")
      (value "Conn_EIGHT8")
      (footprint "CONN2-8")
      (libsource (lib "EIGHT_29") (part "Conn_EIGHT8"))
    )
    (comp (ref "XP3")
      (value "Conn_EIGHT8")
      (footprint "CONN2-8")
      (libsource (lib "EIGHT_29") (part "Conn_EIGHT8"))
    )
    (comp (ref "XP4")
      (value "Conn_EIGHT8")
      (footprint "CONN2-8")
      (libsource (lib "EIGHT_29") (part "Conn_EIGHT8"))
    )
    (comp (ref "XP5") (value "~") (footprint "CONN_2.54_3") (libsource (lib "PANEL") (part "CONNECT_3")))
    (comp (ref "XP6")
      (value "Connect_2.54_8_2")
      (footprint "LEGS8")
      (fields (field (name "PART NUMBER") "BH-8"))
      (libsource (lib "EIGHT_29") (part "Connect_2.54_8_2"))
    )
    (comp (ref "XP7")
      (value "SWD")
      (footprint "CONN_2.54_4")
      (description "PLS-4")
      (fields (field (name "MANUFACTURER") "TRIMMER"))
      (libsource (lib "PANEL") (part "CONNECT_SWD"))
    )
  )
  (nets
    (net (code "1") (name "+3.6V") (class "Default")
      (node (ref "C6") (pin "2") (pinfunction "2_2") (pintype "passive"))
      (node (ref "DA1") (pin "2") (pinfunction "OUT_2") (pintype "passive"))
      (node (ref "DA1") (pin "4") (pinfunction "OUT_4") (pintype "passive"))
      (node (ref "R1") (pin "2") (pinfunction "2_2") (pintype "passive"))
      (node (ref "R2") (pin "2") (pinfunction "2_2") (pintype "passive"))
      (node (ref "R3") (pin "2") (pinfunction "2_2") (pintype "passive"))
      (node (ref "VD1") (pin "1") (pinfunction "1_1") (pintype "passive"))
    )
    (net (code "2") (name "EIGHT0_DP") (class "Default")
      (node (ref "HL1") (pin "1") (pinfunction "1_1") (pintype "passive"))
      (node (ref "HL1") (pin "2") (pinfunction "2_2") (pintype "passive"))
      (node (ref "HL1") (pin "3") (pinfunction "3_3") (pintype "passive"))
      (node (ref "VT8") (pin "3") (pinfunction "3_3") (pintype "passive"))
      (node (ref "XP1") (pin "8") (pinfunction "8_8") (pintype "passive"))
    )
    (net (code "3") (name "EIGHT0_DP_dr") (class "Default")
      (node (ref "DD1") (pin "41") (pinfunction "PB5_41") (pintype "passive"))
      (node (ref "R19") (pin "1") (pinfunction "1_1") (pintype "passive"))
    )
    (net (code "4") (name "EIGHT0_a") (class "Default")
      (node (ref "VT1") (pin "3") (pinfunction "3_3") (pintype "passive"))
      (node (ref "XP1") (pin "1") (pinfunction "1_1") (pintype "passive"))
    )
    (net (code "5") (name "EIGHT0_a_dr") (class "Default")
      (node (ref "DD1") (pin "19") (pinfunction "PB1_19") (pintype "passive"))
      (node (ref "R11") (pin "1") (pinfunction "1_1") (pintype "passive"))
    )
    (net (code "6") (name "EIGHT0_b") (class "Default")
      (node (ref "VT2") (pin "3") (pinfunction "3_3") (pintype "passive"))
      (node (ref "XP1") (pin "2") (pinfunction "2_2") (pintype "passive"))
    )
    (net (code "7") (name "EIGHT0_b_dr") (class "Default")
      (node (ref "DD1") (pin "18") (pinfunction "PB0_18") (pintype "passive"))
      (node (ref "R12") (pin "1") (pinfunction "1_1") (pintype "passive"))
    )
    (net (code "8") (name "EIGHT0_c") (class "Default")
      (node (ref "VT3") (pin "3") (pinfunction "3_3") (pintype "passive"))
      (node (ref "XP1") (pin "3") (pinfunction "3_3") (pintype "passive"))
    )
    (net (code "9") (name "EIGHT0_c_dr") (class "Default")
      (node (ref "DD1") (pin "17") (pinfunction "PA7_17") (pintype "passive"))
      (node (ref "R13") (pin "1") (pinfunction "1_1") (pintype "passive"))
    )
    (net (code "10") (name "EIGHT0_d") (class "Default")
      (node (ref "VT4") (pin "3") (pinfunction "3_3") (pintype "passive"))
      (node (ref "XP1") (pin "4") (pinfunction "4_4") (pintype "passive"))
    )
    (net (code "11") (name "EIGHT0_d_dr") (class "Default")
      (node (ref "DD1") (pin "16") (pinfunction "PA6_16") (pintype "passive"))
      (node (ref "R14") (pin "1") (pinfunction "1_1") (pintype "passive"))
    )
    (net (code "12") (name "EIGHT0_e") (class "Default")
      (node (ref "VT5") (pin "3") (pinfunction "3_3") (pintype "passive"))
      (node (ref "XP1") (pin "5") (pinfunction "5_5") (pintype "passive"))
    )
    (net (code "13") (name "EIGHT0_e_dr") (class "Default")
      (node (ref "DD1") (pin "15") (pinfunction "PA5_15") (pintype "passive"))
      (node (ref "R15") (pin "1") (pinfunction "1_1") (pintype "passive"))
    )
    (net (code "14") (name "EIGHT0_f") (class "Default")
      (node (ref "VT6") (pin "3") (pinfunction "3_3") (pintype "passive"))
      (node (ref "XP1") (pin "6") (pinfunction "6_6") (pintype "passive"))
    )
    (net (code "15") (name "EIGHT0_f_dr") (class "Default")
      (node (ref "DD1") (pin "14") (pinfunction "PA4_14") (pintype "passive"))
      (node (ref "R16") (pin "1") (pinfunction "1_1") (pintype "passive"))
    )
    (net (code "16") (name "EIGHT0_g") (class "Default")
      (node (ref "VT7") (pin "3") (pinfunction "3_3") (pintype "passive"))
      (node (ref "XP1") (pin "7") (pinfunction "7_7") (pintype "passive"))
    )
    (net (code "17") (name "EIGHT0_g_dr") (class "Default")
      (node (ref "DD1") (pin "13") (pinfunction "PA3_13") (pintype "passive"))
      (node (ref "R17") (pin "1") (pinfunction "1_1") (pintype "passive"))
    )
    (net (code "18") (name "EIGHT1_a") (class "Default")
      (node (ref "VT9") (pin "3") (pinfunction "3_3") (pintype "passive"))
      (node (ref "XP2") (pin "1") (pinfunction "1_1") (pintype "passive"))
    )
    (net (code "19") (name "EIGHT1_a_dr") (class "Default")
      (node (ref "DD1") (pin "11") (pinfunction "PA1_11") (pintype "passive"))
      (node (ref "R27") (pin "1") (pinfunction "1_1") (pintype "passive"))
    )
    (net (code "20") (name "EIGHT1_b") (class "Default")
      (node (ref "VT10") (pin "3") (pinfunction "3_3") (pintype "passive"))
      (node (ref "XP2") (pin "2") (pinfunction "2_2") (pintype "passive"))
    )
    (net (code "21") (name "EIGHT1_b_dr") (class "Default")
      (node (ref "DD1") (pin "12") (pinfunction "PA2_12") (pintype "passive"))
      (node (ref "R28") (pin "1") (pinfunction "1_1") (pintype "passive"))
    )
    (net (code "22") (name "EIGHT1_c") (class "Default")
      (node (ref "VT11") (pin "3") (pinfunction "3_3") (pintype "passive"))
      (node (ref "XP2") (pin "3") (pinfunction "3_3") (pintype "passive"))
    )
    (net (code "23") (name "EIGHT1_c_dr") (class "Default")
      (node (ref "DD1") (pin "46") (pinfunction "PB9_46") (pintype "passive"))
      (node (ref "R29") (pin "2") (pinfunction "2_2") (pintype "passive"))
    )
    (net (code "24") (name "EIGHT1_d") (class "Default")
      (node (ref "VT12") (pin "3") (pinfunction "3_3") (pintype "passive"))
      (node (ref "XP2") (pin "4") (pinfunction "4_4") (pintype "passive"))
    )
    (net (code "25") (name "EIGHT1_d_dr") (class "Default")
      (node (ref "DD1") (pin "45") (pinfunction "PB8_45") (pintype "passive"))
      (node (ref "R30") (pin "2") (pinfunction "2_2") (pintype "passive"))
    )
    (net (code "26") (name "EIGHT1_e") (class "Default")
      (node (ref "VT13") (pin "3") (pinfunction "3_3") (pintype "passive"))
      (node (ref "XP2") (pin "5") (pinfunction "5_5") (pintype "passive"))
    )
    (net (code "27") (name "EIGHT1_e_dr") (class "Default")
      (node (ref "DD1") (pin "22") (pinfunction "PB11_22") (pintype "passive"))
      (node (ref "R31") (pin "2") (pinfunction "2_2") (pintype "passive"))
    )
    (net (code "28") (name "EIGHT1_f") (class "Default")
      (node (ref "VT14") (pin "3") (pinfunction "3_3") (pintype "passive"))
      (node (ref "XP2") (pin "6") (pinfunction "6_6") (pintype "passive"))
    )
    (net (code "29") (name "EIGHT1_f_dr") (class "Default")
      (node (ref "DD1") (pin "21") (pinfunction "PB10_21") (pintype "passive"))
      (node (ref "R32") (pin "2") (pinfunction "2_2") (pintype "passive"))
    )
    (net (code "30") (name "EIGHT1_g") (class "Default")
      (node (ref "VT15") (pin "3") (pinfunction "3_3") (pintype "passive"))
      (node (ref "XP2") (pin "7") (pinfunction "7_7") (pintype "passive"))
    )
    (net (code "31") (name "EIGHT1_g_dr") (class "Default")
      (node (ref "DD1") (pin "20") (pinfunction "PB2_20") (pintype "passive"))
      (node (ref "R33") (pin "2") (pinfunction "2_2") (pintype "passive"))
    )
    (net (code "32") (name "EIGHT2_a") (class "Default")
      (node (ref "VT16") (pin "3") (pinfunction "3_3") (pintype "passive"))
      (node (ref "XP3") (pin "1") (pinfunction "1_1") (pintype "passive"))
    )
    (net (code "33") (name "EIGHT2_a_dr") (class "Default")
      (node (ref "DD1") (pin "29") (pinfunction "PA8_29") (pintype "passive"))
      (node (ref "R41") (pin "1") (pinfunction "1_1") (pintype "passive"))
    )
    (net (code "34") (name "EIGHT2_b") (class "Default")
      (node (ref "VT17") (pin "3") (pinfunction "3_3") (pintype "passive"))
      (node (ref "XP3") (pin "2") (pinfunction "2_2") (pintype "passive"))
    )
    (net (code "35") (name "EIGHT2_b_dr") (class "Default")
      (node (ref "DD1") (pin "28") (pinfunction "PB15_28") (pintype "passive"))
      (node (ref "R42") (pin "1") (pinfunction "1_1") (pintype "passive"))
    )
    (net (code "36") (name "EIGHT2_c") (class "Default")
      (node (ref "VT18") (pin "3") (pinfunction "3_3") (pintype "passive"))
      (node (ref "XP3") (pin "3") (pinfunction "3_3") (pintype "passive"))
    )
    (net (code "37") (name "EIGHT2_c_dr") (class "Default")
      (node (ref "DD1") (pin "27") (pinfunction "PB14_27") (pintype "passive"))
      (node (ref "R43") (pin "1") (pinfunction "1_1") (pintype "passive"))
    )
    (net (code "38") (name "EIGHT2_d") (class "Default")
      (node (ref "VT19") (pin "3") (pinfunction "3_3") (pintype "passive"))
      (node (ref "XP3") (pin "4") (pinfunction "4_4") (pintype "passive"))
    )
    (net (code "39") (name "EIGHT2_d_dr") (class "Default")
      (node (ref "DD1") (pin "26") (pinfunction "PB13_26") (pintype "passive"))
      (node (ref "R44") (pin "1") (pinfunction "1_1") (pintype "passive"))
    )
    (net (code "40") (name "EIGHT2_e") (class "Default")
      (node (ref "VT20") (pin "3") (pinfunction "3_3") (pintype "passive"))
      (node (ref "XP3") (pin "5") (pinfunction "5_5") (pintype "passive"))
    )
    (net (code "41") (name "EIGHT2_e_dr") (class "Default")
      (node (ref "DD1") (pin "25") (pinfunction "PB12_25") (pintype "passive"))
      (node (ref "R45") (pin "1") (pinfunction "1_1") (pintype "passive"))
    )
    (net (code "42") (name "EIGHT2_f") (class "Default")
      (node (ref "VT21") (pin "3") (pinfunction "3_3") (pintype "passive"))
      (node (ref "XP3") (pin "6") (pinfunction "6_6") (pintype "passive"))
    )
    (net (code "43") (name "EIGHT2_f_dr") (class "Default")
      (node (ref "DD1") (pin "43") (pinfunction "PB7_43") (pintype "passive"))
      (node (ref "R46") (pin "1") (pinfunction "1_1") (pintype "passive"))
    )
    (net (code "44") (name "EIGHT2_g") (class "Default")
      (node (ref "VT22") (pin "3") (pinfunction "3_3") (pintype "passive"))
      (node (ref "XP3") (pin "7") (pinfunction "7_7") (pintype "passive"))
    )
    (net (code "45") (name "EIGHT2_g_dr") (class "Default")
      (node (ref "C11") (pin "2") (pinfunction "2_2") (pintype "passive"))
      (node (ref "DD1") (pin "37") (pinfunction "PA14_37") (pintype "passive"))
      (node (ref "R47") (pin "1") (pinfunction "1_1") (pintype "passive"))
      (node (ref "XP7") (pin "2") (pinfunction "2_2") (pintype "passive"))
    )
    (net (code "46") (name "EIGHT3_a") (class "Default")
      (node (ref "VT23") (pin "3") (pinfunction "3_3") (pintype "passive"))
      (node (ref "XP4") (pin "1") (pinfunction "1_1") (pintype "passive"))
    )
    (net (code "47") (name "EIGHT3_a_dr") (class "Default")
      (node (ref "DD1") (pin "42") (pinfunction "PB6_42") (pintype "passive"))
      (node (ref "R55") (pin "1") (pinfunction "1_1") (pintype "passive"))
    )
    (net (code "48") (name "EIGHT3_b") (class "Default")
      (node (ref "VT24") (pin "3") (pinfunction "3_3") (pintype "passive"))
      (node (ref "XP4") (pin "2") (pinfunction "2_2") (pintype "passive"))
    )
    (net (code "49") (name "EIGHT3_b_dr") (class "Default")
      (node (ref "DD1") (pin "40") (pinfunction "PB4_40") (pintype "passive"))
      (node (ref "R56") (pin "1") (pinfunction "1_1") (pintype "passive"))
    )
    (net (code "50") (name "EIGHT3_c") (class "Default")
      (node (ref "VT25") (pin "3") (pinfunction "3_3") (pintype "passive"))
      (node (ref "XP4") (pin "3") (pinfunction "3_3") (pintype "passive"))
    )
    (net (code "51") (name "EIGHT3_c_dr") (class "Default")
      (node (ref "DD1") (pin "38") (pinfunction "PA15_38") (pintype "passive"))
      (node (ref "R57") (pin "1") (pinfunction "1_1") (pintype "passive"))
    )
    (net (code "52") (name "EIGHT3_d") (class "Default")
      (node (ref "VT26") (pin "3") (pinfunction "3_3") (pintype "passive"))
      (node (ref "XP4") (pin "4") (pinfunction "4_4") (pintype "passive"))
    )
    (net (code "53") (name "EIGHT3_d_dr") (class "Default")
      (node (ref "DD1") (pin "34") (pinfunction "PA13_34") (pintype "passive"))
      (node (ref "R58") (pin "1") (pinfunction "1_1") (pintype "passive"))
      (node (ref "XP7") (pin "4") (pinfunction "4_4") (pintype "passive"))
    )
    (net (code "54") (name "EIGHT3_e") (class "Default")
      (node (ref "VT27") (pin "3") (pinfunction "3_3") (pintype "passive"))
      (node (ref "XP4") (pin "5") (pinfunction "5_5") (pintype "passive"))
    )
    (net (code "55") (name "EIGHT3_e_dr") (class "Default")
      (node (ref "DD1") (pin "33") (pinfunction "PA12_33") (pintype "passive"))
      (node (ref "R59") (pin "1") (pinfunction "1_1") (pintype "passive"))
    )
    (net (code "56") (name "EIGHT3_f") (class "Default")
      (node (ref "VT28") (pin "3") (pinfunction "3_3") (pintype "passive"))
      (node (ref "XP4") (pin "6") (pinfunction "6_6") (pintype "passive"))
    )
    (net (code "57") (name "EIGHT3_f_dr") (class "Default")
      (node (ref "DD1") (pin "31") (pinfunction "PA10_31") (pintype "passive"))
      (node (ref "R60") (pin "1") (pinfunction "1_1") (pintype "passive"))
    )
    (net (code "58") (name "EIGHT3_g") (class "Default")
      (node (ref "VT29") (pin "3") (pinfunction "3_3") (pintype "passive"))
      (node (ref "XP4") (pin "7") (pinfunction "7_7") (pintype "passive"))
    )
    (net (code "59") (name "EIGHT3_g_dr") (class "Default")
      (node (ref "DD1") (pin "30") (pinfunction "PA9_30") (pintype "passive"))
      (node (ref "R61") (pin "1") (pinfunction "1_1") (pintype "passive"))
    )
    (net (code "60") (name "GND") (class "Default")
      (node (ref "BL1") (pin "2") (pinfunction "GND_2") (pintype "passive"))
      (node (ref "BQ1") (pin "3") (pinfunction "3_3") (pintype "passive"))
      (node (ref "C1") (pin "2") (pinfunction "2_2") (pintype "passive"))
      (node (ref "C10") (pin "1") (pinfunction "1_1") (pintype "passive"))
      (node (ref "C11") (pin "1") (pinfunction "1_1") (pintype "passive"))
      (node (ref "C12") (pin "1") (pinfunction "1_1") (pintype "passive"))
      (node (ref "C13") (pin "1") (pinfunction "1_1") (pintype "passive"))
      (node (ref "C14") (pin "1") (pinfunction "1_1") (pintype "passive"))
      (node (ref "C2") (pin "2") (pinfunction "2_2") (pintype "passive"))
      (node (ref "C3") (pin "2") (pinfunction "2_2") (pintype "passive"))
      (node (ref "C4") (pin "2") (pinfunction "2_2") (pintype "passive"))
      (node (ref "C5") (pin "1") (pinfunction "1_1") (pintype "passive"))
      (node (ref "C6") (pin "1") (pinfunction "1_1") (pintype "passive"))
      (node (ref "C7") (pin "1") (pinfunction "1_1") (pintype "passive"))
      (node (ref "C8") (pin "2") (pinfunction "2_2") (pintype "passive"))
      (node (ref "C9") (pin "1") (pinfunction "1_1") (pintype "passive"))
      (node (ref "DA1") (pin "1") (pinfunction "GND_1") (pintype "passive"))
      (node (ref "DD1") (pin "23") (pinfunction "VSS_1_23") (pintype "passive"))
      (node (ref "DD1") (pin "35") (pinfunction "VSS_2_35") (pintype "passive"))
      (node (ref "DD1") (pin "47") (pinfunction "VSS_3_47") (pintype "passive"))
      (node (ref "DD1") (pin "8") (pinfunction "VSSA_8") (pintype "passive"))
      (node (ref "R10") (pin "2") (pinfunction "2_2") (pintype "passive"))
      (node (ref "R18") (pin "2") (pinfunction "2_2") (pintype "passive"))
      (node (ref "R20") (pin "2") (pinfunction "2_2") (pintype "passive"))
      (node (ref "R21") (pin "2") (pinfunction "2_2") (pintype "passive"))
      (node (ref "R22") (pin "2") (pinfunction "2_2") (pintype "passive"))
      (node (ref "R23") (pin "2") (pinfunction "2_2") (pintype "passive"))
      (node (ref "R24") (pin "2") (pinfunction "2_2") (pintype "passive"))
      (node (ref "R25") (pin "2") (pinfunction "2_2") (pintype "passive"))
      (node (ref "R26") (pin "2") (pinfunction "2_2") (pintype "passive"))
      (node (ref "R34") (pin "2") (pinfunction "2_2") (pintype "passive"))
      (node (ref "R35") (pin "2") (pinfunction "2_2") (pintype "passive"))
      (node (ref "R36") (pin "2") (pinfunction "2_2") (pintype "passive"))
      (node (ref "R37") (pin "2") (pinfunction "2_2") (pintype "passive"))
      (node (ref "R38") (pin "2") (pinfunction "2_2") (pintype "passive"))
      (node (ref "R39") (pin "2") (pinfunction "2_2") (pintype "passive"))
      (node (ref "R4") (pin "2") (pinfunction "2_2") (pintype "passive"))
      (node (ref "R40") (pin "2") (pinfunction "2_2") (pintype "passive"))
      (node (ref "R48") (pin "2") (pinfunction "2_2") (pintype "passive"))
      (node (ref "R49") (pin "2") (pinfunction "2_2") (pintype "passive"))
      (node (ref "R5") (pin "2") (pinfunction "2_2") (pintype "passive"))
      (node (ref "R50") (pin "2") (pinfunction "2_2") (pintype "passive"))
      (node (ref "R51") (pin "2") (pinfunction "2_2") (pintype "passive"))
      (node (ref "R52") (pin "2") (pinfunction "2_2") (pintype "passive"))
      (node (ref "R53") (pin "2") (pinfunction "2_2") (pintype "passive"))
      (node (ref "R54") (pin "2") (pinfunction "2_2") (pintype "passive"))
      (node (ref "R6") (pin "2") (pinfunction "2_2") (pintype "passive"))
      (node (ref "R65") (pin "2") (pinfunction "2_2") (pintype "passive"))
      (node (ref "R7") (pin "2") (pinfunction "2_2") (pintype "passive"))
      (node (ref "R8") (pin "2") (pinfunction "2_2") (pintype "passive"))
      (node (ref "R9") (pin "2") (pinfunction "2_2") (pintype "passive"))
      (node (ref "VT1") (pin "2") (pinfunction "2_2") (pintype "passive"))
      (node (ref "VT10") (pin "2") (pinfunction "2_2") (pintype "passive"))
      (node (ref "VT11") (pin "2") (pinfunction "2_2") (pintype "passive"))
      (node (ref "VT12") (pin "2") (pinfunction "2_2") (pintype "passive"))
      (node (ref "VT13") (pin "2") (pinfunction "2_2") (pintype "passive"))
      (node (ref "VT14") (pin "2") (pinfunction "2_2") (pintype "passive"))
      (node (ref "VT15") (pin "2") (pinfunction "2_2") (pintype "passive"))
      (node (ref "VT16") (pin "2") (pinfunction "2_2") (pintype "passive"))
      (node (ref "VT17") (pin "2") (pinfunction "2_2") (pintype "passive"))
      (node (ref "VT18") (pin "2") (pinfunction "2_2") (pintype "passive"))
      (node (ref "VT19") (pin "2") (pinfunction "2_2") (pintype "passive"))
      (node (ref "VT2") (pin "2") (pinfunction "2_2") (pintype "passive"))
      (node (ref "VT20") (pin "2") (pinfunction "2_2") (pintype "passive"))
      (node (ref "VT21") (pin "2") (pinfunction "2_2") (pintype "passive"))
      (node (ref "VT22") (pin "2") (pinfunction "2_2") (pintype "passive"))
      (node (ref "VT23") (pin "2") (pinfunction "2_2") (pintype "passive"))
      (node (ref "VT24") (pin "2") (pinfunction "2_2") (pintype "passive"))
      (node (ref "VT25") (pin "2") (pinfunction "2_2") (pintype "passive"))
      (node (ref "VT26") (pin "2") (pinfunction "2_2") (pintype "passive"))
      (node (ref "VT27") (pin "2") (pinfunction "2_2") (pintype "passive"))
      (node (ref "VT28") (pin "2") (pinfunction "2_2") (pintype "passive"))
      (node (ref "VT29") (pin "2") (pinfunction "2_2") (pintype "passive"))
      (node (ref "VT3") (pin "2") (pinfunction "2_2") (pintype "passive"))
      (node (ref "VT4") (pin "2") (pinfunction "2_2") (pintype "passive"))
      (node (ref "VT5") (pin "2") (pinfunction "2_2") (pintype "passive"))
      (node (ref "VT6") (pin "2") (pinfunction "2_2") (pintype "passive"))
      (node (ref "VT7") (pin "2") (pinfunction "2_2") (pintype "passive"))
      (node (ref "VT8") (pin "2") (pinfunction "2_2") (pintype "passive"))
      (node (ref "VT9") (pin "2") (pinfunction "2_2") (pintype "passive"))
      (node (ref "XP5") (pin "1") (pinfunction "1_1") (pintype "passive"))
      (node (ref "XP5") (pin "3") (pinfunction "3_3") (pintype "passive"))
      (node (ref "XP6") (pin "7") (pinfunction "7_7") (pintype "passive"))
      (node (ref "XP6") (pin "8") (pinfunction "8_8") (pintype "passive"))
      (node (ref "XP7") (pin "3") (pinfunction "3_3") (pintype "passive"))
    )
    (net (code "61") (name "IRD_OUT") (class "Default")
      (node (ref "DD1") (pin "39") (pinfunction "PB3_39") (pintype "passive"))
      (node (ref "R68") (pin "1") (pinfunction "1_1") (pintype "passive"))
    )
    (net (code "62") (name "Net-(BL1-OUT)") (class "Default")
      (node (ref "BL1") (pin "1") (pinfunction "OUT_1") (pintype "passive"))
      (node (ref "R68") (pin "2") (pinfunction "2_2") (pintype "passive"))
    )
    (net (code "63") (name "Net-(BL1-Vdd)") (class "Default")
      (node (ref "BL1") (pin "3") (pinfunction "Vdd_3") (pintype "passive"))
      (node (ref "C13") (pin "2") (pinfunction "2_2") (pintype "passive"))
      (node (ref "R73") (pin "1") (pinfunction "1_1") (pintype "passive"))
    )
    (net (code "64") (name "Net-(DA1-IN)") (class "Default")
      (node (ref "C14") (pin "2") (pinfunction "2_2") (pintype "passive"))
      (node (ref "DA1") (pin "3") (pinfunction "IN_3") (pintype "passive"))
      (node (ref "XP5") (pin "2") (pinfunction "2_2") (pintype "passive"))
    )
    (net (code "65") (name "Net-(DD1-BOOT0)") (class "Default")
      (node (ref "DD1") (pin "44") (pinfunction "BOOT0_44") (pintype "passive"))
      (node (ref "R65") (pin "1") (pinfunction "1_1") (pintype "passive"))
    )
    (net (code "66") (name "Net-(DD1-PA0-WKUP)") (class "Default")
      (node (ref "DD1") (pin "10") (pinfunction "PA0-WKUP_10") (pintype "passive"))
      (node (ref "R63") (pin "2") (pinfunction "2_2") (pintype "passive"))
    )
    (net (code "67") (name "Net-(DD1-PC14-OSC32_IN)") (class "Default")
      (node (ref "BQ1") (pin "1") (pinfunction "1_1") (pintype "passive"))
      (node (ref "C1") (pin "1") (pinfunction "1_1") (pintype "passive"))
      (node (ref "DD1") (pin "3") (pinfunction "PC14-OSC32_IN_3") (pintype "passive"))
    )
    (net (code "68") (name "Net-(DD1-PC15-OSC32_OUT)") (class "Default")
      (node (ref "BQ1") (pin "2") (pinfunction "2_2") (pintype "passive"))
      (node (ref "C2") (pin "1") (pinfunction "1_1") (pintype "passive"))
      (node (ref "DD1") (pin "4") (pinfunction "PC15-OSC32_OUT_4") (pintype "passive"))
    )
    (net (code "69") (name "Net-(DD1-PD0-OSC_IN)") (class "Default")
      (node (ref "BQ2") (pin "1") (pinfunction "1_1") (pintype "passive"))
      (node (ref "C3") (pin "1") (pinfunction "1_1") (pintype "passive"))
      (node (ref "DD1") (pin "5") (pinfunction "PD0-OSC_IN_5") (pintype "passive"))
    )
    (net (code "70") (name "Net-(DD1-PD1-OSC_OUT)") (class "Default")
      (node (ref "BQ2") (pin "2") (pinfunction "2_2") (pintype "passive"))
      (node (ref "C4") (pin "1") (pinfunction "1_1") (pintype "passive"))
      (node (ref "DD1") (pin "6") (pinfunction "PD1-OSC_OUT_6") (pintype "passive"))
    )
    (net (code "71") (name "Net-(DD1-VBAT)") (class "Default")
      (node (ref "C8") (pin "1") (pinfunction "1_1") (pintype "passive"))
      (node (ref "DD1") (pin "1") (pinfunction "VBAT_1") (pintype "passive"))
      (node (ref "R69") (pin "2") (pinfunction "2_2") (pintype "passive"))
    )
    (net (code "72") (name "Net-(HL1-Pad4)") (class "Default")
      (node (ref "HL1") (pin "4") (pinfunction "4_4") (pintype "passive"))
      (node (ref "R3") (pin "1") (pinfunction "1_1") (pintype "passive"))
    )
    (net (code "73") (name "Net-(HL1-Pad5)") (class "Default")
      (node (ref "HL1") (pin "5") (pinfunction "5_5") (pintype "passive"))
      (node (ref "R2") (pin "1") (pinfunction "1_1") (pintype "passive"))
    )
    (net (code "74") (name "Net-(HL1-Pad6)") (class "Default")
      (node (ref "HL1") (pin "6") (pinfunction "6_6") (pintype "passive"))
      (node (ref "R1") (pin "1") (pinfunction "1_1") (pintype "passive"))
    )
    (net (code "75") (name "Net-(R10-Pad1)") (class "Default")
      (node (ref "R10") (pin "1") (pinfunction "1_1") (pintype "passive"))
      (node (ref "R17") (pin "2") (pinfunction "2_2") (pintype "passive"))
      (node (ref "VT7") (pin "1") (pinfunction "1_1") (pintype "passive"))
    )
    (net (code "76") (name "Net-(R11-Pad2)") (class "Default")
      (node (ref "R11") (pin "2") (pinfunction "2_2") (pintype "passive"))
      (node (ref "R4") (pin "1") (pinfunction "1_1") (pintype "passive"))
      (node (ref "VT1") (pin "1") (pinfunction "1_1") (pintype "passive"))
    )
    (net (code "77") (name "Net-(R12-Pad2)") (class "Default")
      (node (ref "R12") (pin "2") (pinfunction "2_2") (pintype "passive"))
      (node (ref "R5") (pin "1") (pinfunction "1_1") (pintype "passive"))
      (node (ref "VT2") (pin "1") (pinfunction "1_1") (pintype "passive"))
    )
    (net (code "78") (name "Net-(R13-Pad2)") (class "Default")
      (node (ref "R13") (pin "2") (pinfunction "2_2") (pintype "passive"))
      (node (ref "R6") (pin "1") (pinfunction "1_1") (pintype "passive"))
      (node (ref "VT3") (pin "1") (pinfunction "1_1") (pintype "passive"))
    )
    (net (code "79") (name "Net-(R14-Pad2)") (class "Default")
      (node (ref "R14") (pin "2") (pinfunction "2_2") (pintype "passive"))
      (node (ref "R7") (pin "1") (pinfunction "1_1") (pintype "passive"))
      (node (ref "VT4") (pin "1") (pinfunction "1_1") (pintype "passive"))
    )
    (net (code "80") (name "Net-(R15-Pad2)") (class "Default")
      (node (ref "R15") (pin "2") (pinfunction "2_2") (pintype "passive"))
      (node (ref "R8") (pin "1") (pinfunction "1_1") (pintype "passive"))
      (node (ref "VT5") (pin "1") (pinfunction "1_1") (pintype "passive"))
    )
    (net (code "81") (name "Net-(R16-Pad2)") (class "Default")
      (node (ref "R16") (pin "2") (pinfunction "2_2") (pintype "passive"))
      (node (ref "R9") (pin "1") (pinfunction "1_1") (pintype "passive"))
      (node (ref "VT6") (pin "1") (pinfunction "1_1") (pintype "passive"))
    )
    (net (code "82") (name "Net-(R18-Pad1)") (class "Default")
      (node (ref "R18") (pin "1") (pinfunction "1_1") (pintype "passive"))
      (node (ref "R19") (pin "2") (pinfunction "2_2") (pintype "passive"))
      (node (ref "VT8") (pin "1") (pinfunction "1_1") (pintype "passive"))
    )
    (net (code "83") (name "Net-(R20-Pad1)") (class "Default")
      (node (ref "R20") (pin "1") (pinfunction "1_1") (pintype "passive"))
      (node (ref "R27") (pin "2") (pinfunction "2_2") (pintype "passive"))
      (node (ref "VT9") (pin "1") (pinfunction "1_1") (pintype "passive"))
    )
    (net (code "84") (name "Net-(R21-Pad1)") (class "Default")
      (node (ref "R21") (pin "1") (pinfunction "1_1") (pintype "passive"))
      (node (ref "R28") (pin "2") (pinfunction "2_2") (pintype "passive"))
      (node (ref "VT10") (pin "1") (pinfunction "1_1") (pintype "passive"))
    )
    (net (code "85") (name "Net-(R22-Pad1)") (class "Default")
      (node (ref "R22") (pin "1") (pinfunction "1_1") (pintype "passive"))
      (node (ref "R29") (pin "1") (pinfunction "1_1") (pintype "passive"))
      (node (ref "VT11") (pin "1") (pinfunction "1_1") (pintype "passive"))
    )
    (net (code "86") (name "Net-(R23-Pad1)") (class "Default")
      (node (ref "R23") (pin "1") (pinfunction "1_1") (pintype "passive"))
      (node (ref "R30") (pin "1") (pinfunction "1_1") (pintype "passive"))
      (node (ref "VT12") (pin "1") (pinfunction "1_1") (pintype "passive"))
    )
    (net (code "87") (name "Net-(R24-Pad1)") (class "Default")
      (node (ref "R24") (pin "1") (pinfunction "1_1") (pintype "passive"))
      (node (ref "R31") (pin "1") (pinfunction "1_1") (pintype "passive"))
      (node (ref "VT13") (pin "1") (pinfunction "1_1") (pintype "passive"))
    )
    (net (code "88") (name "Net-(R25-Pad1)") (class "Default")
      (node (ref "R25") (pin "1") (pinfunction "1_1") (pintype "passive"))
      (node (ref "R32") (pin "1") (pinfunction "1_1") (pintype "passive"))
      (node (ref "VT14") (pin "1") (pinfunction "1_1") (pintype "passive"))
    )
    (net (code "89") (name "Net-(R26-Pad1)") (class "Default")
      (node (ref "R26") (pin "1") (pinfunction "1_1") (pintype "passive"))
      (node (ref "R33") (pin "1") (pinfunction "1_1") (pintype "passive"))
      (node (ref "VT15") (pin "1") (pinfunction "1_1") (pintype "passive"))
    )
    (net (code "90") (name "Net-(R34-Pad1)") (class "Default")
      (node (ref "R34") (pin "1") (pinfunction "1_1") (pintype "passive"))
      (node (ref "R41") (pin "2") (pinfunction "2_2") (pintype "passive"))
      (node (ref "VT16") (pin "1") (pinfunction "1_1") (pintype "passive"))
    )
    (net (code "91") (name "Net-(R35-Pad1)") (class "Default")
      (node (ref "R35") (pin "1") (pinfunction "1_1") (pintype "passive"))
      (node (ref "R42") (pin "2") (pinfunction "2_2") (pintype "passive"))
      (node (ref "VT17") (pin "1") (pinfunction "1_1") (pintype "passive"))
    )
    (net (code "92") (name "Net-(R36-Pad1)") (class "Default")
      (node (ref "R36") (pin "1") (pinfunction "1_1") (pintype "passive"))
      (node (ref "R43") (pin "2") (pinfunction "2_2") (pintype "passive"))
      (node (ref "VT18") (pin "1") (pinfunction "1_1") (pintype "passive"))
    )
    (net (code "93") (name "Net-(R37-Pad1)") (class "Default")
      (node (ref "R37") (pin "1") (pinfunction "1_1") (pintype "passive"))
      (node (ref "R44") (pin "2") (pinfunction "2_2") (pintype "passive"))
      (node (ref "VT19") (pin "1") (pinfunction "1_1") (pintype "passive"))
    )
    (net (code "94") (name "Net-(R38-Pad1)") (class "Default")
      (node (ref "R38") (pin "1") (pinfunction "1_1") (pintype "passive"))
      (node (ref "R45") (pin "2") (pinfunction "2_2") (pintype "passive"))
      (node (ref "VT20") (pin "1") (pinfunction "1_1") (pintype "passive"))
    )
    (net (code "95") (name "Net-(R39-Pad1)") (class "Default")
      (node (ref "R39") (pin "1") (pinfunction "1_1") (pintype "passive"))
      (node (ref "R46") (pin "2") (pinfunction "2_2") (pintype "passive"))
      (node (ref "VT21") (pin "1") (pinfunction "1_1") (pintype "passive"))
    )
    (net (code "96") (name "Net-(R40-Pad1)") (class "Default")
      (node (ref "R40") (pin "1") (pinfunction "1_1") (pintype "passive"))
      (node (ref "R47") (pin "2") (pinfunction "2_2") (pintype "passive"))
      (node (ref "VT22") (pin "1") (pinfunction "1_1") (pintype "passive"))
    )
    (net (code "97") (name "Net-(R48-Pad1)") (class "Default")
      (node (ref "R48") (pin "1") (pinfunction "1_1") (pintype "passive"))
      (node (ref "R55") (pin "2") (pinfunction "2_2") (pintype "passive"))
      (node (ref "VT23") (pin "1") (pinfunction "1_1") (pintype "passive"))
    )
    (net (code "98") (name "Net-(R49-Pad1)") (class "Default")
      (node (ref "R49") (pin "1") (pinfunction "1_1") (pintype "passive"))
      (node (ref "R56") (pin "2") (pinfunction "2_2") (pintype "passive"))
      (node (ref "VT24") (pin "1") (pinfunction "1_1") (pintype "passive"))
    )
    (net (code "99") (name "Net-(R50-Pad1)") (class "Default")
      (node (ref "R50") (pin "1") (pinfunction "1_1") (pintype "passive"))
      (node (ref "R57") (pin "2") (pinfunction "2_2") (pintype "passive"))
      (node (ref "VT25") (pin "1") (pinfunction "1_1") (pintype "passive"))
    )
    (net (code "100") (name "Net-(R51-Pad1)") (class "Default")
      (node (ref "R51") (pin "1") (pinfunction "1_1") (pintype "passive"))
      (node (ref "R58") (pin "2") (pinfunction "2_2") (pintype "passive"))
      (node (ref "VT26") (pin "1") (pinfunction "1_1") (pintype "passive"))
    )
    (net (code "101") (name "Net-(R52-Pad1)") (class "Default")
      (node (ref "R52") (pin "1") (pinfunction "1_1") (pintype "passive"))
      (node (ref "R59") (pin "2") (pinfunction "2_2") (pintype "passive"))
      (node (ref "VT27") (pin "1") (pinfunction "1_1") (pintype "passive"))
    )
    (net (code "102") (name "Net-(R53-Pad1)") (class "Default")
      (node (ref "R53") (pin "1") (pinfunction "1_1") (pintype "passive"))
      (node (ref "R60") (pin "2") (pinfunction "2_2") (pintype "passive"))
      (node (ref "VT28") (pin "1") (pinfunction "1_1") (pintype "passive"))
    )
    (net (code "103") (name "Net-(R54-Pad1)") (class "Default")
      (node (ref "R54") (pin "1") (pinfunction "1_1") (pintype "passive"))
      (node (ref "R61") (pin "2") (pinfunction "2_2") (pintype "passive"))
      (node (ref "VT29") (pin "1") (pinfunction "1_1") (pintype "passive"))
    )
    (net (code "104") (name "Net-(R69-Pad1)") (class "Default")
      (node (ref "R69") (pin "1") (pinfunction "1_1") (pintype "passive"))
      (node (ref "VD1") (pin "2") (pinfunction "2_2") (pintype "passive"))
    )
    (net (code "105") (name "Net-(R72-Pad1)") (class "Default")
      (node (ref "R72") (pin "1") (pinfunction "1_1") (pintype "passive"))
      (node (ref "XP7") (pin "1") (pinfunction "1_1") (pintype "passive"))
    )
    (net (code "106") (name "PPS") (class "Default")
      (node (ref "R62") (pin "2") (pinfunction "2_2") (pintype "passive"))
      (node (ref "R63") (pin "1") (pinfunction "1_1") (pintype "passive"))
      (node (ref "XP6") (pin "5") (pinfunction "5_5") (pintype "passive"))
      (node (ref "XP6") (pin "6") (pinfunction "6_6") (pintype "passive"))
    )
    (net (code "107") (name "RESETn") (class "Default")
      (node (ref "C5") (pin "2") (pinfunction "2_2") (pintype "passive"))
      (node (ref "DD1") (pin "7") (pinfunction "NRST_7") (pintype "passive"))
      (node (ref "R66") (pin "2") (pinfunction "2_2") (pintype "passive"))
    )
    (net (code "108") (name "UART_RX") (class "Default")
      (node (ref "DD1") (pin "32") (pinfunction "PA11_32") (pintype "passive"))
      (node (ref "XP6") (pin "3") (pinfunction "3_3") (pintype "passive"))
      (node (ref "XP6") (pin "4") (pinfunction "4_4") (pintype "passive"))
    )
    (net (code "109") (name "VCC") (class "Default")
      (node (ref "C10") (pin "2") (pinfunction "2_2") (pintype "passive"))
      (node (ref "C12") (pin "2") (pinfunction "2_2") (pintype "passive"))
      (node (ref "C7") (pin "2") (pinfunction "2_2") (pintype "passive"))
      (node (ref "C9") (pin "2") (pinfunction "2_2") (pintype "passive"))
      (node (ref "DD1") (pin "24") (pinfunction "VDD_1_24") (pintype "passive"))
      (node (ref "DD1") (pin "36") (pinfunction "VDD_2_36") (pintype "passive"))
      (node (ref "DD1") (pin "48") (pinfunction "VDD_3_48") (pintype "passive"))
      (node (ref "DD1") (pin "9") (pinfunction "VDDA_9") (pintype "passive"))
      (node (ref "R62") (pin "1") (pinfunction "1_1") (pintype "passive"))
      (node (ref "R66") (pin "1") (pinfunction "1_1") (pintype "passive"))
      (node (ref "R72") (pin "2") (pinfunction "2_2") (pintype "passive"))
      (node (ref "R73") (pin "2") (pinfunction "2_2") (pintype "passive"))
      (node (ref "VD1") (pin "3") (pinfunction "3_3") (pintype "passive"))
      (node (ref "XP6") (pin "1") (pinfunction "1_1") (pintype "passive"))
      (node (ref "XP6") (pin "2") (pinfunction "2_2") (pintype "passive"))
    )
    (net (code "110") (name "unconnected-(DD1-PC13-TAMP-RTC-Pad2)") (class "Default")
      (node (ref "DD1") (pin "2") (pinfunction "PC13-TAMP-RTC_2") (pintype "passive"))
    )
    (net (code "111") (name "unconnected-(XP2-Pad8)") (class "Default")
      (node (ref "XP2") (pin "8") (pinfunction "8_8") (pintype "passive"))
    )
    (net (code "112") (name "unconnected-(XP3-Pad8)") (class "Default")
      (node (ref "XP3") (pin "8") (pinfunction "8_8") (pintype "passive"))
    )
    (net (code "113") (name "unconnected-(XP4-Pad8)") (class "Default")
      (node (ref "XP4") (pin "8") (pinfunction "8_8") (pintype "passive"))
    )
  )
)
